# RS232_2xNPN_Mirrored.net
KiCad netlist of a schematic drawn in EAGLE
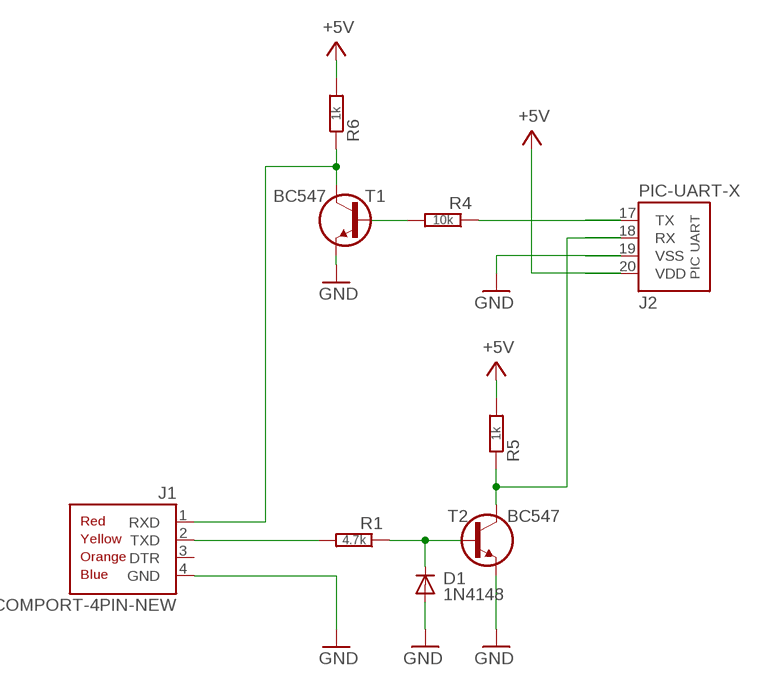
[diagram p0: schematic, sheet 1]

(export (version "E")
  (design (tool "Eeschema 10.0.6"))
  (components
    (comp (ref "D1")
      (value "1N4148")
      (footprint "eagle-import:DO34-5")
      (libsource (lib "eagle-import") (part "1N414834-5"))
    )
    (comp (ref "J1")
      (value "COMPORT-4PIN-NEW")
      (footprint "eagle-import:RS232-4PIN-NEW")
      (libsource (lib "eagle-import") (part "COMPORT-4PIN-NEW"))
    )
    (comp (ref "J2")
      (value "PIC-UART-X")
      (footprint "eagle-import:PIC-UART-X")
      (libsource (lib "eagle-import") (part "PIC-UART-X"))
    )
    (comp (ref "R1")
      (value "4.7k")
      (footprint "eagle-import:0202_7")
      (libsource (lib "eagle-import") (part "R0202/7"))
    )
    (comp (ref "R4")
      (value "10k")
      (footprint "eagle-import:0202_7")
      (libsource (lib "eagle-import") (part "R0202/7"))
    )
    (comp (ref "R5")
      (value "1k")
      (footprint "eagle-import:0202_7-V")
      (libsource (lib "eagle-import") (part "R0202/7-V"))
    )
    (comp (ref "R6")
      (value "1k")
      (footprint "eagle-import:0202_7")
      (libsource (lib "eagle-import") (part "R0202/7"))
    )
    (comp (ref "T1")
      (value "BC547")
      (footprint "eagle-import:TO92-CBE")
      (libsource (lib "eagle-import") (part "BC547CBE"))
    )
    (comp (ref "T2")
      (value "BC547")
      (footprint "eagle-import:TO92-CBE")
      (libsource (lib "eagle-import") (part "BC547CBE"))
    )
  )
  (nets
    (net (code "1") (name "+5V") (class "Default")
      (node (ref "J2") (pin "20") (pinfunction "VDD_20") (pintype "passive"))
      (node (ref "R5") (pin "2") (pinfunction "2_2") (pintype "passive"))
      (node (ref "R6") (pin "2") (pinfunction "2_2") (pintype "passive"))
    )
    (net (code "2") (name "GND") (class "Default")
      (node (ref "D1") (pin "A") (pinfunction "A_A") (pintype "passive"))
      (node (ref "J1") (pin "4") (pinfunction "GND_4") (pintype "passive"))
      (node (ref "J2") (pin "19") (pinfunction "VSS_19") (pintype "passive"))
      (node (ref "T1") (pin "E") (pinfunction "E_E") (pintype "passive"))
      (node (ref "T2") (pin "E") (pinfunction "E_E") (pintype "passive"))
    )
    (net (code "3") (name "Net-(D1-PadC)") (class "Default")
      (node (ref "D1") (pin "C") (pinfunction "C_C") (pintype "passive"))
      (node (ref "R1") (pin "1") (pinfunction "1_1") (pintype "passive"))
      (node (ref "T2") (pin "B") (pinfunction "B_B") (pintype "passive"))
    )
    (net (code "4") (name "Net-(J1-RXD)") (class "Default")
      (node (ref "J1") (pin "1") (pinfunction "RXD_1") (pintype "passive"))
      (node (ref "R6") (pin "1") (pinfunction "1_1") (pintype "passive"))
      (node (ref "T1") (pin "C") (pinfunction "C_C") (pintype "passive"))
    )
    (net (code "5") (name "Net-(J1-TXD)") (class "Default")
      (node (ref "J1") (pin "2") (pinfunction "TXD_2") (pintype "passive"))
      (node (ref "R1") (pin "2") (pinfunction "2_2") (pintype "passive"))
    )
    (net (code "6") (name "Net-(J2-RX)") (class "Default")
      (node (ref "J2") (pin "18") (pinfunction "RX_18") (pintype "passive"))
      (node (ref "R5") (pin "1") (pinfunction "1_1") (pintype "passive"))
      (node (ref "T2") (pin "C") (pinfunction "C_C") (pintype "passive"))
    )
    (net (code "7") (name "Net-(J2-TX)") (class "Default")
      (node (ref "J2") (pin "17") (pinfunction "TX_17") (pintype "passive"))
      (node (ref "R4") (pin "1") (pinfunction "1_1") (pintype "passive"))
    )
    (net (code "8") (name "Net-(R4-Pad2)") (class "Default")
      (node (ref "R4") (pin "2") (pinfunction "2_2") (pintype "passive"))
      (node (ref "T1") (pin "B") (pinfunction "B_B") (pintype "passive"))
    )
    (net (code "9") (name "unconnected-(J1-DTR-Pad3)") (class "Default")
      (node (ref "J1") (pin "3") (pinfunction "DTR_3") (pintype "passive"))
    )
  )
)
